# BLAST_TNG_PSD.net
KiCad netlist of a schematic drawn in EAGLE
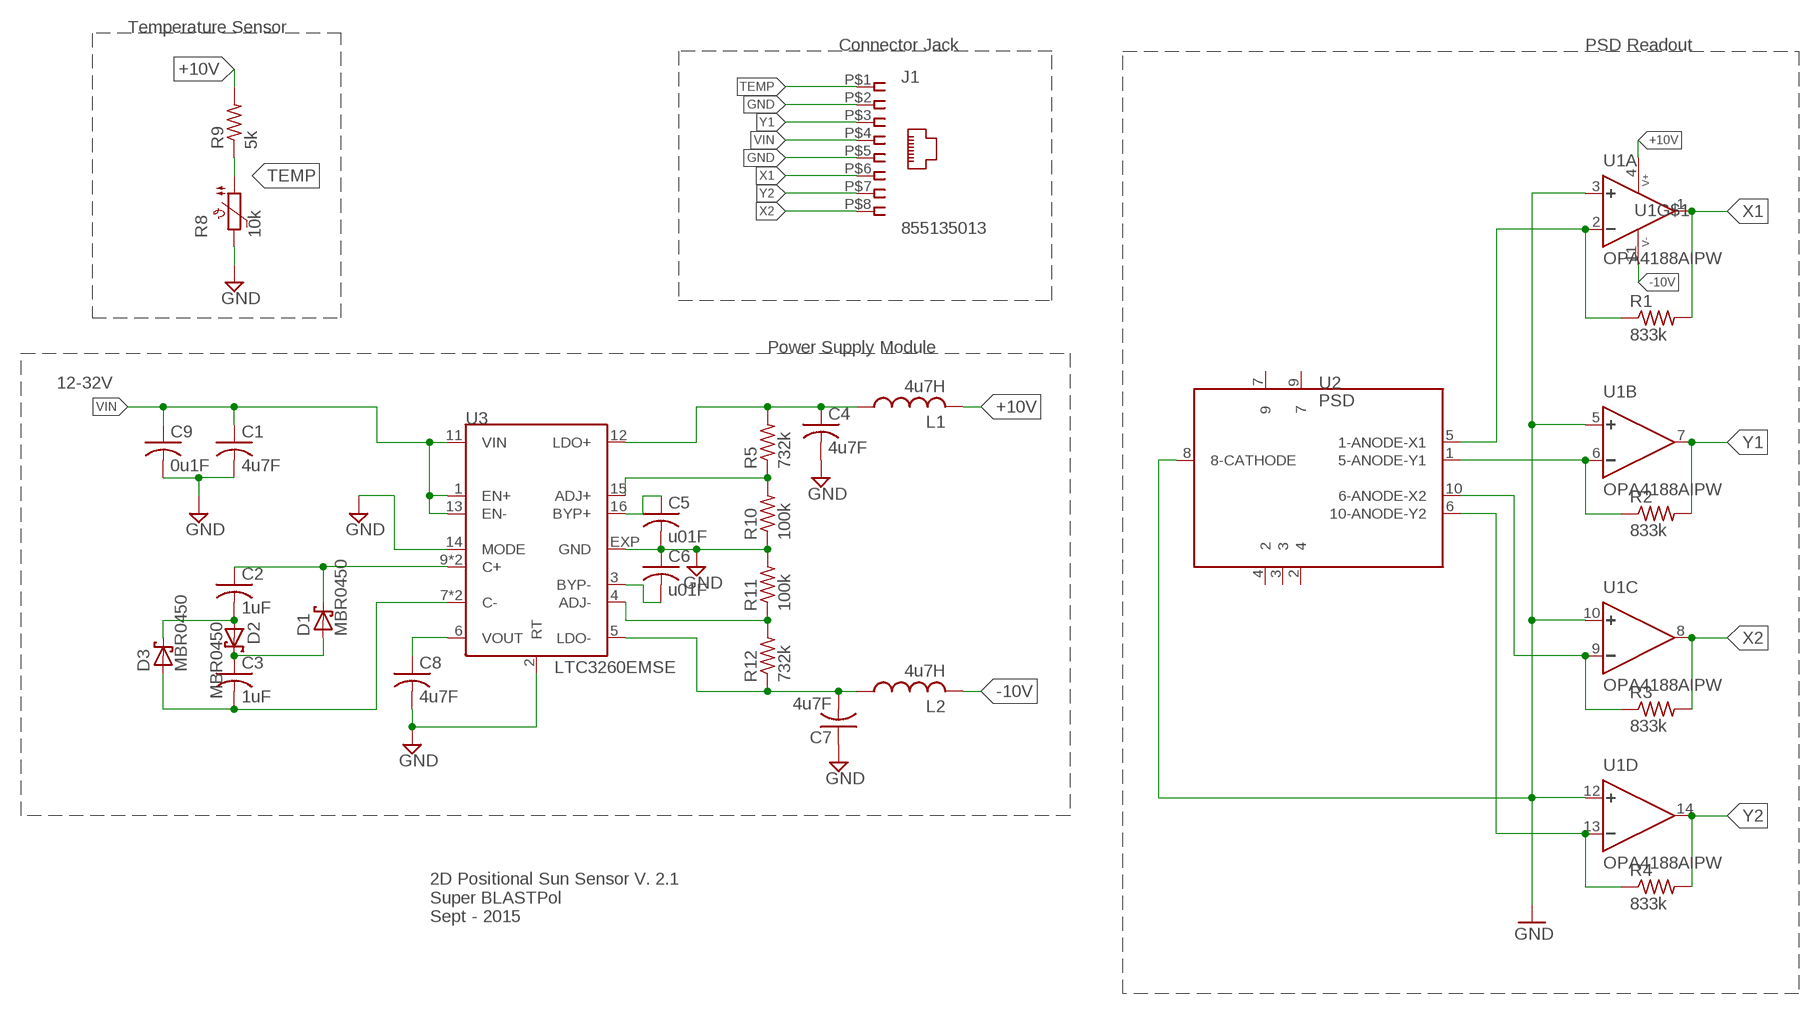
[diagram p0: schematic, sheet 1]

(export (version "E")
  (design (tool "Eeschema 10.0.6"))
  (components
    (comp (ref "C1")
      (value "4u7F")
      (footprint "eagle-import:C1210")
      (fields (field (name "MPN") "CL31A475KOHNNNE"))
      (libsource (lib "eagle-import") (part "C-USC1210"))
    )
    (comp (ref "C2")
      (value "1uF")
      (footprint "eagle-import:C1206")
      (libsource (lib "eagle-import") (part "C-USC1206"))
    )
    (comp (ref "C3")
      (value "1uF")
      (footprint "eagle-import:C1206")
      (libsource (lib "eagle-import") (part "C-USC1206"))
    )
    (comp (ref "C4")
      (value "4u7F")
      (footprint "eagle-import:C1210")
      (fields (field (name "MPN") "CL31A475KOHNNNE"))
      (libsource (lib "eagle-import") (part "C-USC1210"))
    )
    (comp (ref "C5")
      (value "u01F")
      (footprint "eagle-import:C0805")
      (libsource (lib "eagle-import") (part "C-USC0805"))
    )
    (comp (ref "C6")
      (value "u01F")
      (footprint "eagle-import:C0805")
      (libsource (lib "eagle-import") (part "C-USC0805"))
    )
    (comp (ref "C7")
      (value "4u7F")
      (footprint "eagle-import:C1210")
      (fields (field (name "MPN") "CL31A475KOHNNNE"))
      (libsource (lib "eagle-import") (part "C-USC1210"))
    )
    (comp (ref "C8")
      (value "4u7F")
      (footprint "eagle-import:C1210")
      (fields (field (name "MPN") "CL31A475KOHNNNE"))
      (libsource (lib "eagle-import") (part "C-USC1210"))
    )
    (comp (ref "C9")
      (value "0u1F")
      (footprint "eagle-import:C0805")
      (libsource (lib "eagle-import") (part "C-USC0805"))
    )
    (comp (ref "D1")
      (value "MBR0450")
      (footprint "eagle-import:SOD123")
      (libsource (lib "eagle-import") (part "MBR0450"))
    )
    (comp (ref "D2")
      (value "MBR0450")
      (footprint "eagle-import:SOD123")
      (libsource (lib "eagle-import") (part "MBR0450"))
    )
    (comp (ref "D3")
      (value "MBR0450")
      (footprint "eagle-import:SOD123")
      (libsource (lib "eagle-import") (part "MBR0450"))
    )
    (comp (ref "J1")
      (value "855135013")
      (footprint "eagle-import:855135013")
      (fields (field (name "MPN") "85513-5013"))
      (libsource (lib "eagle-import") (part "855135013"))
    )
    (comp (ref "L1")
      (value "4u7H")
      (footprint "eagle-import:L2012C")
      (libsource (lib "eagle-import") (part "L-USL2012C"))
    )
    (comp (ref "L2")
      (value "4u7H")
      (footprint "eagle-import:L2012C")
      (libsource (lib "eagle-import") (part "L-USL2012C"))
    )
    (comp (ref "R1")
      (value "833k")
      (footprint "eagle-import:M0805")
      (libsource (lib "eagle-import") (part "R-US_M0805"))
    )
    (comp (ref "R2")
      (value "833k")
      (footprint "eagle-import:M0805")
      (libsource (lib "eagle-import") (part "R-US_M0805"))
    )
    (comp (ref "R3")
      (value "833k")
      (footprint "eagle-import:M0805")
      (libsource (lib "eagle-import") (part "R-US_M0805"))
    )
    (comp (ref "R4")
      (value "833k")
      (footprint "eagle-import:M0805")
      (libsource (lib "eagle-import") (part "R-US_M0805"))
    )
    (comp (ref "R5")
      (value "732k")
      (footprint "eagle-import:R0805")
      (libsource (lib "eagle-import") (part "rcl_R-US_R0805"))
    )
    (comp (ref "R8")
      (value "10k")
      (footprint "eagle-import:L3216C")
      (fields (field (name "MPN") "KPTL-3216CGCK"))
      (libsource (lib "eagle-import") (part "VISHAY-TFPT1206"))
    )
    (comp (ref "R9")
      (value "5k")
      (footprint "eagle-import:R0805")
      (libsource (lib "eagle-import") (part "rcl_R-US_R0805"))
    )
    (comp (ref "R10")
      (value "100k")
      (footprint "eagle-import:R0805")
      (libsource (lib "eagle-import") (part "rcl_R-US_R0805"))
    )
    (comp (ref "R11")
      (value "100k")
      (footprint "eagle-import:R0805")
      (libsource (lib "eagle-import") (part "rcl_R-US_R0805"))
    )
    (comp (ref "R12")
      (value "732k")
      (footprint "eagle-import:R0805")
      (libsource (lib "eagle-import") (part "rcl_R-US_R0805"))
    )
    (comp (ref "U1")
      (value "OPA4188AIPW")
      (footprint "eagle-import:TSSOP14")
      (fields (field (name "OC_NEWARK") "unknown"))
      (libsource (lib "eagle-import") (part "OPA4188PWAI"))
    )
    (comp (ref "U2")
      (value "PSD")
      (footprint "eagle-import:PSD-S5991")
      (libsource (lib "eagle-import") (part "PSD-S5991"))
    )
    (comp (ref "U3")
      (value "LTC3260EMSE")
      (footprint "eagle-import:MSOP16")
      (libsource (lib "eagle-import") (part "LTC3260MSEE"))
    )
  )
  (nets
    (net (code "1") (name "+10V") (class "Default")
      (node (ref "L1") (pin "2") (pinfunction "2_2") (pintype "passive"))
      (node (ref "R9") (pin "2") (pinfunction "2_2") (pintype "passive"))
      (node (ref "U1") (pin "4") (pinfunction "V+_4") (pintype "power_in"))
    )
    (net (code "2") (name "-10V") (class "Default")
      (node (ref "L2") (pin "2") (pinfunction "2_2") (pintype "passive"))
      (node (ref "U1") (pin "11") (pinfunction "V-_11") (pintype "power_in"))
    )
    (net (code "3") (name "GND") (class "Default")
      (node (ref "C1") (pin "2") (pinfunction "2_2") (pintype "passive"))
      (node (ref "C4") (pin "2") (pinfunction "2_2") (pintype "passive"))
      (node (ref "C5") (pin "2") (pinfunction "2_2") (pintype "passive"))
      (node (ref "C6") (pin "1") (pinfunction "1_1") (pintype "passive"))
      (node (ref "C7") (pin "1") (pinfunction "1_1") (pintype "passive"))
      (node (ref "C8") (pin "2") (pinfunction "2_2") (pintype "passive"))
      (node (ref "C9") (pin "2") (pinfunction "2_2") (pintype "passive"))
      (node (ref "J1") (pin "P$2") (pinfunction "2_P$2") (pintype "passive"))
      (node (ref "J1") (pin "P$5") (pinfunction "5_P$5") (pintype "passive"))
      (node (ref "R10") (pin "1") (pinfunction "1_1") (pintype "passive"))
      (node (ref "R11") (pin "2") (pinfunction "2_2") (pintype "passive"))
      (node (ref "R8") (pin "2") (pinfunction "2_2") (pintype "passive"))
      (node (ref "U1") (pin "10") (pinfunction "+_10") (pintype "input"))
      (node (ref "U1") (pin "12") (pinfunction "+_12") (pintype "input"))
      (node (ref "U1") (pin "3") (pinfunction "+_3") (pintype "input"))
      (node (ref "U1") (pin "5") (pinfunction "+_5") (pintype "input"))
      (node (ref "U2") (pin "8") (pinfunction "8-CATHODE_8") (pintype "bidirectional"))
      (node (ref "U3") (pin "14") (pinfunction "MODE_14") (pintype "bidirectional"))
      (node (ref "U3") (pin "2") (pinfunction "RT_2") (pintype "bidirectional"))
      (node (ref "U3") (pin "EXP") (pinfunction "GND_EXP") (pintype "bidirectional"))
    )
    (net (code "4") (name "Net-(C2-Pad1)") (class "Default")
      (node (ref "C2") (pin "1") (pinfunction "1_1") (pintype "passive"))
      (node (ref "D1") (pin "C") (pinfunction "C_C") (pintype "passive"))
      (node (ref "U3") (pin "10") (pinfunction "C+_10") (pintype "bidirectional"))
      (node (ref "U3") (pin "9") (pinfunction "C+_9") (pintype "bidirectional"))
    )
    (net (code "5") (name "Net-(C2-Pad2)") (class "Default")
      (node (ref "C2") (pin "2") (pinfunction "2_2") (pintype "passive"))
      (node (ref "D2") (pin "A") (pinfunction "A_A") (pintype "passive"))
      (node (ref "D3") (pin "C") (pinfunction "C_C") (pintype "passive"))
    )
    (net (code "6") (name "Net-(C3-Pad1)") (class "Default")
      (node (ref "C3") (pin "1") (pinfunction "1_1") (pintype "passive"))
      (node (ref "D1") (pin "A") (pinfunction "A_A") (pintype "passive"))
      (node (ref "D2") (pin "C") (pinfunction "C_C") (pintype "passive"))
    )
    (net (code "7") (name "Net-(C3-Pad2)") (class "Default")
      (node (ref "C3") (pin "2") (pinfunction "2_2") (pintype "passive"))
      (node (ref "D3") (pin "A") (pinfunction "A_A") (pintype "passive"))
      (node (ref "U3") (pin "7") (pinfunction "C-_7") (pintype "bidirectional"))
      (node (ref "U3") (pin "8") (pinfunction "C-_8") (pintype "bidirectional"))
    )
    (net (code "8") (name "Net-(U1A--)") (class "Default")
      (node (ref "R1") (pin "1") (pinfunction "1_1") (pintype "passive"))
      (node (ref "U1") (pin "2") (pinfunction "-_2") (pintype "input"))
      (node (ref "U2") (pin "5") (pinfunction "1-ANODE-X1_5") (pintype "bidirectional"))
    )
    (net (code "9") (name "Net-(U1B--)") (class "Default")
      (node (ref "R2") (pin "1") (pinfunction "1_1") (pintype "passive"))
      (node (ref "U1") (pin "6") (pinfunction "-_6") (pintype "input"))
      (node (ref "U2") (pin "1") (pinfunction "5-ANODE-Y1_1") (pintype "bidirectional"))
    )
    (net (code "10") (name "Net-(U1C--)") (class "Default")
      (node (ref "R3") (pin "1") (pinfunction "1_1") (pintype "passive"))
      (node (ref "U1") (pin "9") (pinfunction "-_9") (pintype "input"))
      (node (ref "U2") (pin "10") (pinfunction "6-ANODE-X2_10") (pintype "bidirectional"))
    )
    (net (code "11") (name "Net-(U1D--)") (class "Default")
      (node (ref "R4") (pin "1") (pinfunction "1_1") (pintype "passive"))
      (node (ref "U1") (pin "13") (pinfunction "-_13") (pintype "input"))
      (node (ref "U2") (pin "6") (pinfunction "10-ANODE-Y2_6") (pintype "bidirectional"))
    )
    (net (code "12") (name "Net-(U3-ADJ+)") (class "Default")
      (node (ref "R10") (pin "2") (pinfunction "2_2") (pintype "passive"))
      (node (ref "R5") (pin "1") (pinfunction "1_1") (pintype "passive"))
      (node (ref "U3") (pin "15") (pinfunction "ADJ+_15") (pintype "bidirectional"))
    )
    (net (code "13") (name "Net-(U3-ADJ-)") (class "Default")
      (node (ref "R11") (pin "1") (pinfunction "1_1") (pintype "passive"))
      (node (ref "R12") (pin "2") (pinfunction "2_2") (pintype "passive"))
      (node (ref "U3") (pin "4") (pinfunction "ADJ-_4") (pintype "bidirectional"))
    )
    (net (code "14") (name "Net-(U3-BYP+)") (class "Default")
      (node (ref "C5") (pin "1") (pinfunction "1_1") (pintype "passive"))
      (node (ref "U3") (pin "16") (pinfunction "BYP+_16") (pintype "bidirectional"))
    )
    (net (code "15") (name "Net-(U3-BYP-)") (class "Default")
      (node (ref "C6") (pin "2") (pinfunction "2_2") (pintype "passive"))
      (node (ref "U3") (pin "3") (pinfunction "BYP-_3") (pintype "bidirectional"))
    )
    (net (code "16") (name "Net-(U3-LDO+)") (class "Default")
      (node (ref "C4") (pin "1") (pinfunction "1_1") (pintype "passive"))
      (node (ref "L1") (pin "1") (pinfunction "1_1") (pintype "passive"))
      (node (ref "R5") (pin "2") (pinfunction "2_2") (pintype "passive"))
      (node (ref "U3") (pin "12") (pinfunction "LDO+_12") (pintype "bidirectional"))
    )
    (net (code "17") (name "Net-(U3-LDO-)") (class "Default")
      (node (ref "C7") (pin "2") (pinfunction "2_2") (pintype "passive"))
      (node (ref "L2") (pin "1") (pinfunction "1_1") (pintype "passive"))
      (node (ref "R12") (pin "1") (pinfunction "1_1") (pintype "passive"))
      (node (ref "U3") (pin "5") (pinfunction "LDO-_5") (pintype "bidirectional"))
    )
    (net (code "18") (name "Net-(U3-VOUT)") (class "Default")
      (node (ref "C8") (pin "1") (pinfunction "1_1") (pintype "passive"))
      (node (ref "U3") (pin "6") (pinfunction "VOUT_6") (pintype "bidirectional"))
    )
    (net (code "19") (name "TEMP") (class "Default")
      (node (ref "J1") (pin "P$1") (pinfunction "1_P$1") (pintype "passive"))
      (node (ref "R8") (pin "1") (pinfunction "1_1") (pintype "passive"))
      (node (ref "R9") (pin "1") (pinfunction "1_1") (pintype "passive"))
    )
    (net (code "20") (name "VIN") (class "Default")
      (node (ref "C1") (pin "1") (pinfunction "1_1") (pintype "passive"))
      (node (ref "C9") (pin "1") (pinfunction "1_1") (pintype "passive"))
      (node (ref "J1") (pin "P$4") (pinfunction "4_P$4") (pintype "passive"))
      (node (ref "U3") (pin "1") (pinfunction "EN+_1") (pintype "bidirectional"))
      (node (ref "U3") (pin "11") (pinfunction "VIN_11") (pintype "bidirectional"))
      (node (ref "U3") (pin "13") (pinfunction "EN-_13") (pintype "bidirectional"))
    )
    (net (code "21") (name "X1") (class "Default")
      (node (ref "J1") (pin "P$6") (pinfunction "6_P$6") (pintype "passive"))
      (node (ref "R1") (pin "2") (pinfunction "2_2") (pintype "passive"))
      (node (ref "U1") (pin "1") (pinfunction "OUT_1") (pintype "output"))
    )
    (net (code "22") (name "X2") (class "Default")
      (node (ref "J1") (pin "P$8") (pinfunction "8_P$8") (pintype "passive"))
      (node (ref "R3") (pin "2") (pinfunction "2_2") (pintype "passive"))
      (node (ref "U1") (pin "8") (pinfunction "OUT_8") (pintype "output"))
    )
    (net (code "23") (name "Y1") (class "Default")
      (node (ref "J1") (pin "P$3") (pinfunction "3_P$3") (pintype "passive"))
      (node (ref "R2") (pin "2") (pinfunction "2_2") (pintype "passive"))
      (node (ref "U1") (pin "7") (pinfunction "OUT_7") (pintype "output"))
    )
    (net (code "24") (name "Y2") (class "Default")
      (node (ref "J1") (pin "P$7") (pinfunction "7_P$7") (pintype "passive"))
      (node (ref "R4") (pin "2") (pinfunction "2_2") (pintype "passive"))
      (node (ref "U1") (pin "14") (pinfunction "OUT_14") (pintype "output"))
    )
    (net (code "25") (name "unconnected-(U2-2-Pad4)") (class "Default")
      (node (ref "U2") (pin "4") (pinfunction "2_4") (pintype "bidirectional"))
    )
    (net (code "26") (name "unconnected-(U2-4-Pad2)") (class "Default")
      (node (ref "U2") (pin "2") (pinfunction "4_2") (pintype "bidirectional"))
    )
    (net (code "27") (name "unconnected-(U2-7-Pad9)") (class "Default")
      (node (ref "U2") (pin "9") (pinfunction "7_9") (pintype "bidirectional"))
    )
    (net (code "28") (name "unconnected-(U2-9-Pad7)") (class "Default")
      (node (ref "U2") (pin "7") (pinfunction "9_7") (pintype "bidirectional"))
    )
    (net (code "29") (name "unconnected-(U2-Pad3)") (class "Default")
      (node (ref "U2") (pin "3") (pinfunction "3_3") (pintype "bidirectional"))
    )
  )
)
